# USB_CONNS.net
KiCad netlist of a schematic drawn in Altium Designer
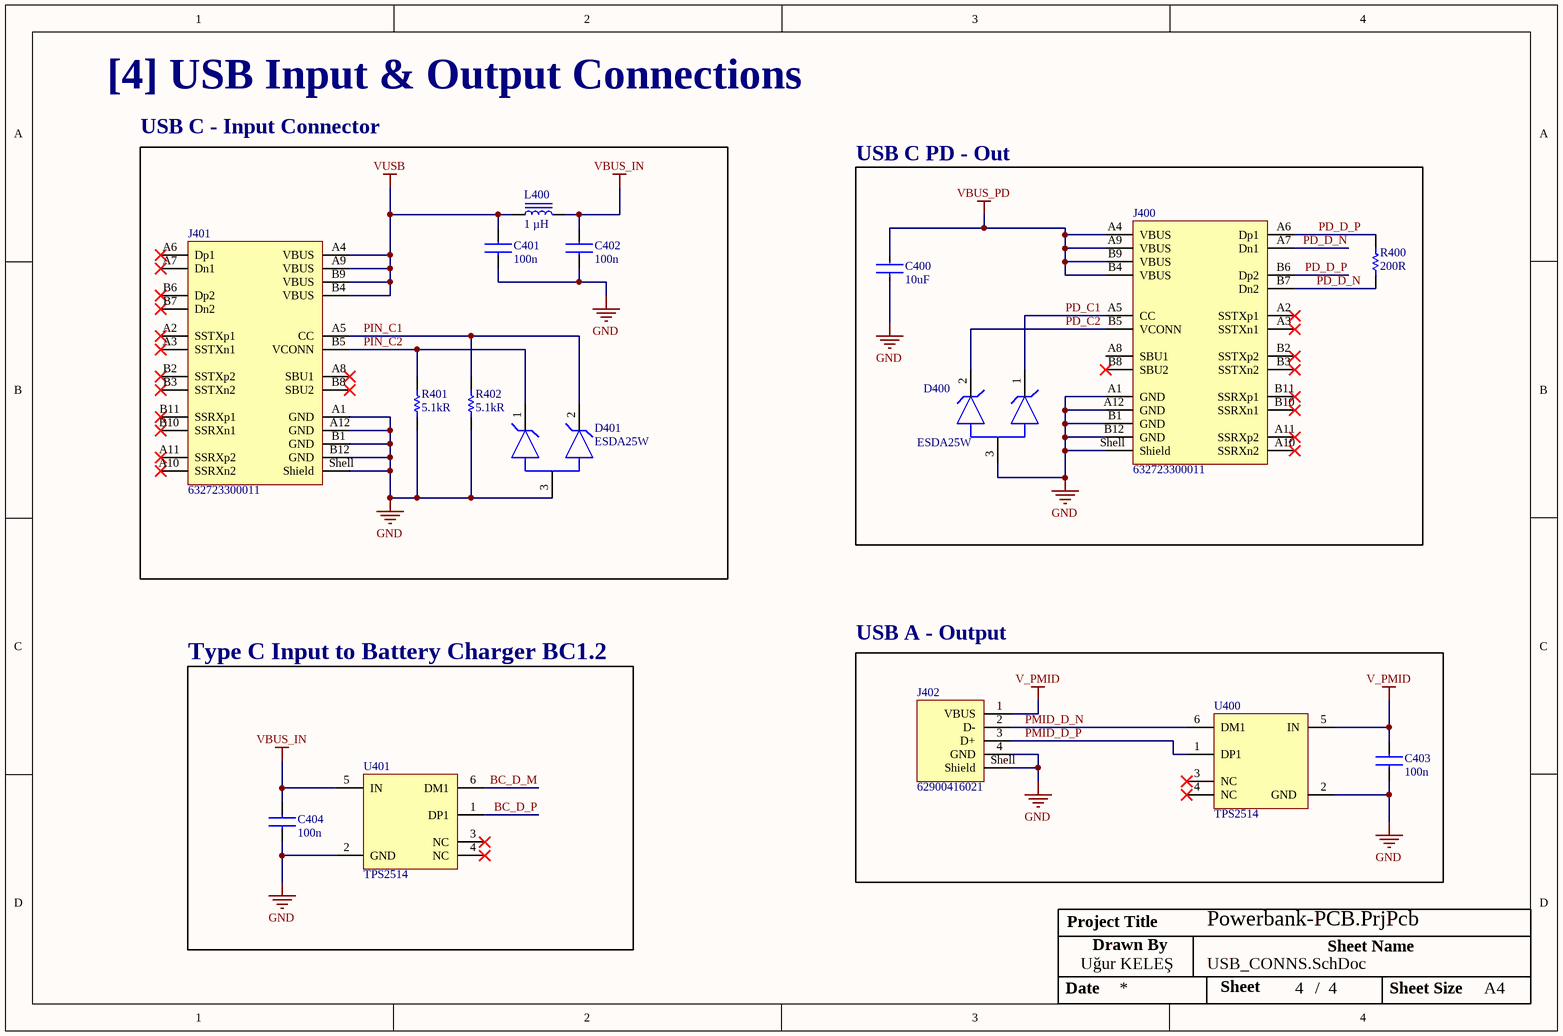
[diagram p0: USB_CONNS.SchDoc]

(export (version "E")
  (design (tool "Eeschema 10.0.6"))
  (components
    (comp (ref "C400")
      (value "GRT31CR61H106ME01L")
      (footprint "FP-GRT31C-0_2-IPC_A")
      (description "CAP CER 10UF 50V X5R 1206")
      (fields (field (name "CAPACITANCE") "10uF") (field (name "TOLERANCE") "20%"))
      (libsource (lib "Altium Content Vault") (part "11868f565c42a9108669ba33697ecf6"))
    )
    (comp (ref "C401")
      (value "100n")
      (footprint "CAP CER 0402")
      (fields (field (name "DESIGNED BY") "UK"))
      (libsource (lib "UKLIB") (part "CAP CER GENERIC 0402"))
    )
    (comp (ref "C402")
      (value "100n")
      (footprint "CAP CER 0402")
      (fields (field (name "DESIGNED BY") "UK"))
      (libsource (lib "UKLIB") (part "CAP CER GENERIC 0402"))
    )
    (comp (ref "C403")
      (value "100n")
      (footprint "CAP CER 0402")
      (fields (field (name "DESIGNED BY") "UK"))
      (libsource (lib "UKLIB") (part "CAP CER GENERIC 0402"))
    )
    (comp (ref "C404")
      (value "100n")
      (footprint "CAP CER 0402")
      (fields (field (name "DESIGNED BY") "UK"))
      (libsource (lib "UKLIB") (part "CAP CER GENERIC 0402"))
    )
    (comp (ref "D400")
      (value "ESDA25W")
      (footprint "FP-SOT323-3L-IPC_C")
      (description "TVS DIODE 24VWM SOT323")
      (libsource (lib "Altium Content Vault") (part "dab4d306e483478a9de7b7922f83869"))
    )
    (comp (ref "D401")
      (value "ESDA25W")
      (footprint "FP-SOT323-3L-IPC_C")
      (description "TVS DIODE 24VWM SOT323")
      (libsource (lib "Altium Content Vault") (part "dab4d306e483478a9de7b7922f83869"))
    )
    (comp (ref "J400")
      (value "632723300011")
      (footprint "632723300011")
      (libsource (lib "Altium Content Vault") (part "USB 3.1_Type C_Receptacle_1 Port"))
    )
    (comp (ref "J401")
      (value "632723300011")
      (footprint "632723300011")
      (libsource (lib "") (part "USB 3.1_Type C_Receptacle_1 Port_1"))
    )
    (comp (ref "J402")
      (value "62900416021")
      (footprint "62900416021")
      (libsource (lib "Altium Content Vault") (part "USB 2.0_Type A_Receptacle_1 Port"))
    )
    (comp (ref "L400")
      (value "1 µH")
      (footprint "TDK MLZ1608")
      (description "FIXED IND 1UH 700MA 110 MOHM SMD")
      (fields (field (name "PART NUMBER") "MLZ1608N1R0LT000") (field (name "MANUFACTURER") "TDK Corporation"))
      (libsource (lib "Celestial Altium Library - altium_library") (part "Inductor"))
    )
    (comp (ref "R400")
      (value "200R")
      (footprint "RESC1005X40X25ML05T05")
      (fields
        (field (name "PART NUMBER") "CRCW0402200RJNED")
        (field (name "MANUFACTURER") "Vishay Dale")
        (field (name "TOLERANCE") "5%")
      )
      (libsource (lib "Altium Content Vault") (part "RES"))
    )
    (comp (ref "R401")
      (value "5.1kR")
      (footprint "RESC1005X40X25NL05T10")
      (fields
        (field (name "PART NUMBER") "RC0402FR-075K1L")
        (field (name "MANUFACTURER") "Yageo / Phycomp")
        (field (name "TOLERANCE") "1%")
      )
      (libsource (lib "Altium Content Vault") (part "RES"))
    )
    (comp (ref "R402")
      (value "5.1kR")
      (footprint "RESC1005X40X25NL05T10")
      (fields
        (field (name "PART NUMBER") "RC0402FR-075K1L")
        (field (name "MANUFACTURER") "Yageo / Phycomp")
        (field (name "TOLERANCE") "1%")
      )
      (libsource (lib "Altium Content Vault") (part "RES"))
    )
    (comp (ref "U400")
      (value "TPS2514")
      (footprint "SOT23-6L")
      (description "Power Supply Support Circuit, Fixed, 1 Channel, PDSO6")
      (fields
        (field (name "MANUFACTURER") "Texas Instruments")
        (field (name "MANUFACTURER PART NUMBER") "TPS2514DBVR")
        (field (name "DESIGNED BY") "UK")
      )
      (libsource (lib "UKLIB") (part "TPS2514"))
    )
    (comp (ref "U401")
      (value "TPS2514")
      (footprint "SOT23-6L")
      (description "Power Supply Support Circuit, Fixed, 1 Channel, PDSO6")
      (fields
        (field (name "MANUFACTURER") "Texas Instruments")
        (field (name "MANUFACTURER PART NUMBER") "TPS2514DBVR")
        (field (name "DESIGNED BY") "UK")
      )
      (libsource (lib "") (part "TPS2514_1"))
    )
  )
  (nets
    (net (code "1") (name "/BC_D_M") (class "Default")
      (node (ref "U401") (pin "6") (pinfunction "DM1_6") (pintype "passive"))
    )
    (net (code "2") (name "/BC_D_P") (class "Default")
      (node (ref "U401") (pin "1") (pinfunction "DP1_1") (pintype "passive"))
    )
    (net (code "3") (name "/PD_C1") (class "Default")
      (node (ref "D400") (pin "1") (pinfunction "1_CATHODE_1") (pintype "passive"))
      (node (ref "J400") (pin "A5") (pinfunction "CC_A5") (pintype "passive"))
    )
    (net (code "4") (name "/PD_C2") (class "Default")
      (node (ref "D400") (pin "2") (pinfunction "2_CATHODE_2") (pintype "passive"))
      (node (ref "J400") (pin "B5") (pinfunction "VCONN_B5") (pintype "passive"))
    )
    (net (code "5") (name "/PD_D_N") (class "Default")
      (node (ref "J400") (pin "A7") (pinfunction "Dn1_A7") (pintype "passive"))
      (node (ref "J400") (pin "B7") (pinfunction "Dn2_B7") (pintype "passive"))
      (node (ref "R400") (pin "1") (pinfunction "1_1") (pintype "passive"))
    )
    (net (code "6") (name "/PD_D_P") (class "Default")
      (node (ref "J400") (pin "A6") (pinfunction "Dp1_A6") (pintype "passive"))
      (node (ref "J400") (pin "B6") (pinfunction "Dp2_B6") (pintype "passive"))
      (node (ref "R400") (pin "2") (pinfunction "2_2") (pintype "passive"))
    )
    (net (code "7") (name "/PIN_C1") (class "Default")
      (node (ref "D401") (pin "2") (pinfunction "2_CATHODE_2") (pintype "passive"))
      (node (ref "J401") (pin "A5") (pinfunction "CC_A5") (pintype "passive"))
      (node (ref "R402") (pin "1") (pinfunction "1_1") (pintype "passive"))
    )
    (net (code "8") (name "/PIN_C2") (class "Default")
      (node (ref "D401") (pin "1") (pinfunction "1_CATHODE_1") (pintype "passive"))
      (node (ref "J401") (pin "B5") (pinfunction "VCONN_B5") (pintype "passive"))
      (node (ref "R401") (pin "1") (pinfunction "1_1") (pintype "passive"))
    )
    (net (code "9") (name "/PMID_D_N") (class "Default")
      (node (ref "J402") (pin "2") (pinfunction "D-_2") (pintype "passive"))
      (node (ref "U400") (pin "6") (pinfunction "DM1_6") (pintype "passive"))
    )
    (net (code "10") (name "/PMID_D_P") (class "Default")
      (node (ref "J402") (pin "3") (pinfunction "D+_3") (pintype "passive"))
      (node (ref "U400") (pin "1") (pinfunction "DP1_1") (pintype "passive"))
    )
    (net (code "11") (name "GND") (class "Default")
      (node (ref "C400") (pin "1") (pinfunction "1_1") (pintype "passive"))
      (node (ref "C401") (pin "1") (pinfunction "1_1") (pintype "passive"))
      (node (ref "C402") (pin "1") (pinfunction "1_1") (pintype "passive"))
      (node (ref "C403") (pin "1") (pinfunction "1_1") (pintype "passive"))
      (node (ref "C404") (pin "1") (pinfunction "1_1") (pintype "passive"))
      (node (ref "D400") (pin "3") (pinfunction "COMMON_ANODE_3") (pintype "passive"))
      (node (ref "D401") (pin "3") (pinfunction "COMMON_ANODE_3") (pintype "passive"))
      (node (ref "J400") (pin "A1") (pinfunction "GND_A1") (pintype "passive"))
      (node (ref "J400") (pin "A12") (pinfunction "GND_A12") (pintype "passive"))
      (node (ref "J400") (pin "B1") (pinfunction "GND_B1") (pintype "passive"))
      (node (ref "J400") (pin "B12") (pinfunction "GND_B12") (pintype "passive"))
      (node (ref "J400") (pin "Shell") (pinfunction "Shield_Shell") (pintype "passive"))
      (node (ref "J401") (pin "A1") (pinfunction "GND_A1") (pintype "passive"))
      (node (ref "J401") (pin "A12") (pinfunction "GND_A12") (pintype "passive"))
      (node (ref "J401") (pin "B1") (pinfunction "GND_B1") (pintype "passive"))
      (node (ref "J401") (pin "B12") (pinfunction "GND_B12") (pintype "passive"))
      (node (ref "J401") (pin "Shell") (pinfunction "Shield_Shell") (pintype "passive"))
      (node (ref "J402") (pin "4") (pinfunction "GND_4") (pintype "passive"))
      (node (ref "J402") (pin "Shell") (pinfunction "Shield_Shell") (pintype "passive"))
      (node (ref "R401") (pin "2") (pinfunction "2_2") (pintype "passive"))
      (node (ref "R402") (pin "2") (pinfunction "2_2") (pintype "passive"))
      (node (ref "U400") (pin "2") (pinfunction "GND_2") (pintype "passive"))
      (node (ref "U401") (pin "2") (pinfunction "GND_2") (pintype "passive"))
    )
    (net (code "12") (name "VBUS_IN") (class "Default")
      (node (ref "C402") (pin "2") (pinfunction "2_2") (pintype "passive"))
      (node (ref "C404") (pin "2") (pinfunction "2_2") (pintype "passive"))
      (node (ref "L400") (pin "2") (pinfunction "2_2") (pintype "passive"))
      (node (ref "U401") (pin "5") (pinfunction "IN_5") (pintype "passive"))
    )
    (net (code "13") (name "VBUS_PD") (class "Default")
      (node (ref "C400") (pin "2") (pinfunction "2_2") (pintype "passive"))
      (node (ref "J400") (pin "A4") (pinfunction "VBUS_A4") (pintype "passive"))
      (node (ref "J400") (pin "A9") (pinfunction "VBUS_A9") (pintype "passive"))
      (node (ref "J400") (pin "B4") (pinfunction "VBUS_B4") (pintype "passive"))
      (node (ref "J400") (pin "B9") (pinfunction "VBUS_B9") (pintype "passive"))
    )
    (net (code "14") (name "VUSB") (class "Default")
      (node (ref "C401") (pin "2") (pinfunction "2_2") (pintype "passive"))
      (node (ref "J401") (pin "A4") (pinfunction "VBUS_A4") (pintype "passive"))
      (node (ref "J401") (pin "A9") (pinfunction "VBUS_A9") (pintype "passive"))
      (node (ref "J401") (pin "B4") (pinfunction "VBUS_B4") (pintype "passive"))
      (node (ref "J401") (pin "B9") (pinfunction "VBUS_B9") (pintype "passive"))
      (node (ref "L400") (pin "1") (pinfunction "1_1") (pintype "passive"))
    )
    (net (code "15") (name "V_PMID") (class "Default")
      (node (ref "C403") (pin "2") (pinfunction "2_2") (pintype "passive"))
      (node (ref "J402") (pin "1") (pinfunction "VBUS_1") (pintype "passive"))
      (node (ref "U400") (pin "5") (pinfunction "IN_5") (pintype "passive"))
    )
    (net (code "16") (name "unconnected-(J400-SBU1-PadA8)") (class "Default")
      (node (ref "J400") (pin "A8") (pinfunction "SBU1_A8") (pintype "passive"))
    )
    (net (code "17") (name "unconnected-(J400-SBU2-PadB8)") (class "Default")
      (node (ref "J400") (pin "B8") (pinfunction "SBU2_B8") (pintype "passive+no_connect"))
    )
    (net (code "18") (name "unconnected-(J400-SSRXn1-PadB10)") (class "Default")
      (node (ref "J400") (pin "B10") (pinfunction "SSRXn1_B10") (pintype "passive+no_connect"))
    )
    (net (code "19") (name "unconnected-(J400-SSRXn2-PadA10)") (class "Default")
      (node (ref "J400") (pin "A10") (pinfunction "SSRXn2_A10") (pintype "passive+no_connect"))
    )
    (net (code "20") (name "unconnected-(J400-SSRXp1-PadB11)") (class "Default")
      (node (ref "J400") (pin "B11") (pinfunction "SSRXp1_B11") (pintype "passive+no_connect"))
    )
    (net (code "21") (name "unconnected-(J400-SSRXp2-PadA11)") (class "Default")
      (node (ref "J400") (pin "A11") (pinfunction "SSRXp2_A11") (pintype "passive+no_connect"))
    )
    (net (code "22") (name "unconnected-(J400-SSTXn1-PadA3)") (class "Default")
      (node (ref "J400") (pin "A3") (pinfunction "SSTXn1_A3") (pintype "passive+no_connect"))
    )
    (net (code "23") (name "unconnected-(J400-SSTXn2-PadB3)") (class "Default")
      (node (ref "J400") (pin "B3") (pinfunction "SSTXn2_B3") (pintype "passive+no_connect"))
    )
    (net (code "24") (name "unconnected-(J400-SSTXp1-PadA2)") (class "Default")
      (node (ref "J400") (pin "A2") (pinfunction "SSTXp1_A2") (pintype "passive+no_connect"))
    )
    (net (code "25") (name "unconnected-(J400-SSTXp2-PadB2)") (class "Default")
      (node (ref "J400") (pin "B2") (pinfunction "SSTXp2_B2") (pintype "passive+no_connect"))
    )
    (net (code "26") (name "unconnected-(J401-Dn1-PadA7)") (class "Default")
      (node (ref "J401") (pin "A7") (pinfunction "Dn1_A7") (pintype "passive+no_connect"))
    )
    (net (code "27") (name "unconnected-(J401-Dn2-PadB7)") (class "Default")
      (node (ref "J401") (pin "B7") (pinfunction "Dn2_B7") (pintype "passive+no_connect"))
    )
    (net (code "28") (name "unconnected-(J401-Dp1-PadA6)") (class "Default")
      (node (ref "J401") (pin "A6") (pinfunction "Dp1_A6") (pintype "passive+no_connect"))
    )
    (net (code "29") (name "unconnected-(J401-Dp2-PadB6)") (class "Default")
      (node (ref "J401") (pin "B6") (pinfunction "Dp2_B6") (pintype "passive+no_connect"))
    )
    (net (code "30") (name "unconnected-(J401-SBU1-PadA8)") (class "Default")
      (node (ref "J401") (pin "A8") (pinfunction "SBU1_A8") (pintype "passive+no_connect"))
    )
    (net (code "31") (name "unconnected-(J401-SBU2-PadB8)") (class "Default")
      (node (ref "J401") (pin "B8") (pinfunction "SBU2_B8") (pintype "passive+no_connect"))
    )
    (net (code "32") (name "unconnected-(J401-SSRXn1-PadB10)") (class "Default")
      (node (ref "J401") (pin "B10") (pinfunction "SSRXn1_B10") (pintype "passive+no_connect"))
    )
    (net (code "33") (name "unconnected-(J401-SSRXn2-PadA10)") (class "Default")
      (node (ref "J401") (pin "A10") (pinfunction "SSRXn2_A10") (pintype "passive+no_connect"))
    )
    (net (code "34") (name "unconnected-(J401-SSRXp1-PadB11)") (class "Default")
      (node (ref "J401") (pin "B11") (pinfunction "SSRXp1_B11") (pintype "passive+no_connect"))
    )
    (net (code "35") (name "unconnected-(J401-SSRXp2-PadA11)") (class "Default")
      (node (ref "J401") (pin "A11") (pinfunction "SSRXp2_A11") (pintype "passive+no_connect"))
    )
    (net (code "36") (name "unconnected-(J401-SSTXn1-PadA3)") (class "Default")
      (node (ref "J401") (pin "A3") (pinfunction "SSTXn1_A3") (pintype "passive+no_connect"))
    )
    (net (code "37") (name "unconnected-(J401-SSTXn2-PadB3)") (class "Default")
      (node (ref "J401") (pin "B3") (pinfunction "SSTXn2_B3") (pintype "passive+no_connect"))
    )
    (net (code "38") (name "unconnected-(J401-SSTXp1-PadA2)") (class "Default")
      (node (ref "J401") (pin "A2") (pinfunction "SSTXp1_A2") (pintype "passive+no_connect"))
    )
    (net (code "39") (name "unconnected-(J401-SSTXp2-PadB2)") (class "Default")
      (node (ref "J401") (pin "B2") (pinfunction "SSTXp2_B2") (pintype "passive+no_connect"))
    )
    (net (code "40") (name "unconnected-(U400-NC-Pad3)") (class "Default")
      (node (ref "U400") (pin "3") (pinfunction "NC_3") (pintype "passive+no_connect"))
    )
    (net (code "41") (name "unconnected-(U400-NC-Pad4)") (class "Default")
      (node (ref "U400") (pin "4") (pinfunction "NC_4") (pintype "passive+no_connect"))
    )
    (net (code "42") (name "unconnected-(U401-NC-Pad3)") (class "Default")
      (node (ref "U401") (pin "3") (pinfunction "NC_3") (pintype "passive+no_connect"))
    )
    (net (code "43") (name "unconnected-(U401-NC-Pad4)") (class "Default")
      (node (ref "U401") (pin "4") (pinfunction "NC_4") (pintype "passive+no_connect"))
    )
  )
)
